# W5500.net
KiCad netlist of a schematic drawn in Altium Designer
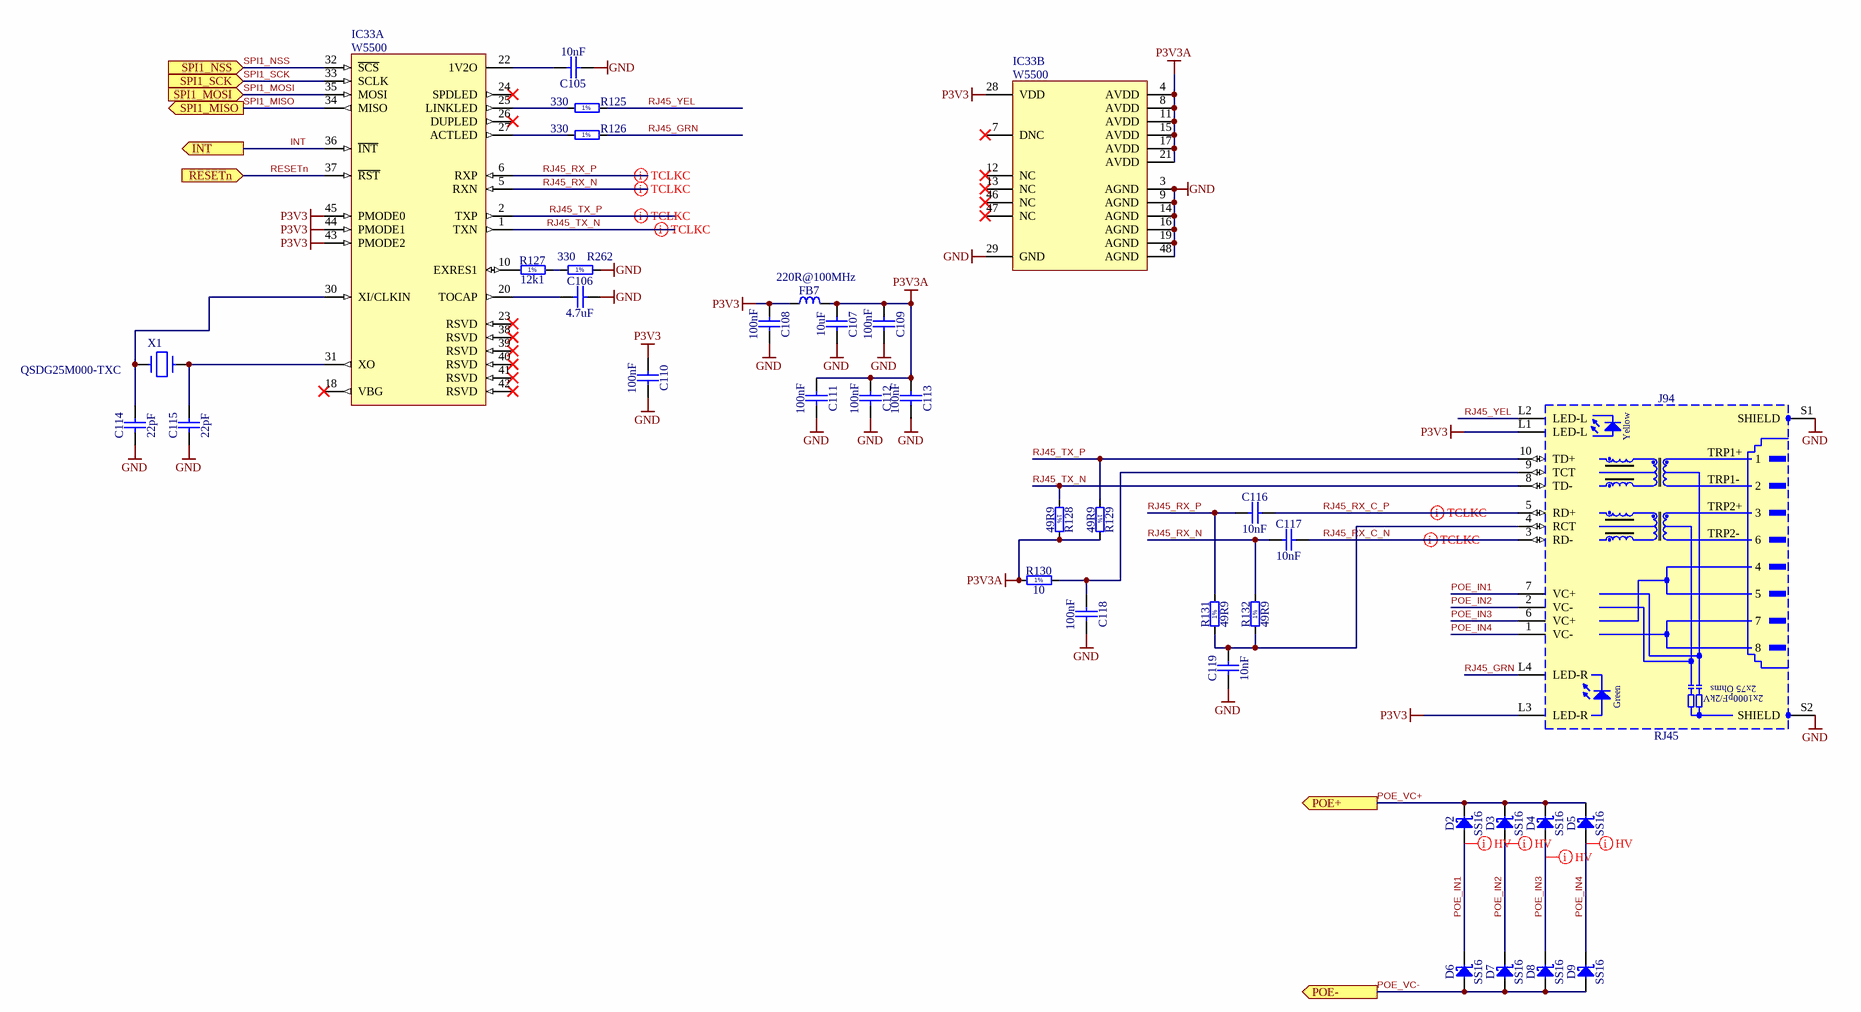
[diagram p0: W5500.SchDoc]

(export (version "E")
  (design (tool "Eeschema 10.0.6"))
  (components
    (comp (ref "C105")
      (value "10nF")
      (footprint "CAPC1608X87N")
      (description "Non-polarised capacitor")
      (fields
        (field (name "PART NUMBER") "CC0603_10NF_50V_5%_C0G")
        (field (name "VOLTAGE") "50V")
        (field (name "AUTHOR") "CERN DEM JLC")
      )
      (libsource (lib "Capacitors") (part "Capacitor - non polarized"))
    )
    (comp (ref "C106")
      (value "4.7uF")
      (footprint "CAPC1608X90N")
      (description "Non-polarised capacitor")
      (fields
        (field (name "PART NUMBER") "CC0603_4.7UF_25V_10%_X5R")
        (field (name "VOLTAGE") "25V")
        (field (name "AUTHOR") "CERN DEM JLC")
      )
      (libsource (lib "Capacitors") (part "Capacitor - non polarized"))
    )
    (comp (ref "C107")
      (value "10uF")
      (footprint "CAPC2012X135N")
      (description "Non-polarised capacitor")
      (fields
        (field (name "PART NUMBER") "CC0805_10UF_16V_10%_X5R")
        (field (name "VOLTAGE") "16V")
        (field (name "AUTHOR") "CERN DEM JLC")
      )
      (libsource (lib "Capacitors") (part "Capacitor - non polarized"))
    )
    (comp (ref "C108")
      (value "100nF")
      (footprint "CAPC1005X55N")
      (description "Non-polarised capacitor")
      (fields
        (field (name "PART NUMBER") "CC0402_100NF_16V_10%_X7R")
        (field (name "VOLTAGE") "16V")
        (field (name "AUTHOR") "CERN DEM JLC")
      )
      (libsource (lib "Capacitors") (part "Capacitor - non polarized"))
    )
    (comp (ref "C109")
      (value "100nF")
      (footprint "CAPC1005X55N")
      (description "Non-polarised capacitor")
      (fields
        (field (name "PART NUMBER") "CC0402_100NF_16V_10%_X7R")
        (field (name "VOLTAGE") "16V")
        (field (name "AUTHOR") "CERN DEM JLC")
      )
      (libsource (lib "Capacitors") (part "Capacitor - non polarized"))
    )
    (comp (ref "C110")
      (value "100nF")
      (footprint "CAPC1005X55N")
      (description "Non-polarised capacitor")
      (fields
        (field (name "PART NUMBER") "CC0402_100NF_16V_10%_X7R")
        (field (name "VOLTAGE") "16V")
        (field (name "AUTHOR") "CERN DEM JLC")
      )
      (libsource (lib "Capacitors") (part "Capacitor - non polarized"))
    )
    (comp (ref "C111")
      (value "100nF")
      (footprint "CAPC1005X55N")
      (description "Non-polarised capacitor")
      (fields
        (field (name "PART NUMBER") "CC0402_100NF_16V_10%_X7R")
        (field (name "VOLTAGE") "16V")
        (field (name "AUTHOR") "CERN DEM JLC")
      )
      (libsource (lib "Capacitors") (part "Capacitor - non polarized"))
    )
    (comp (ref "C112")
      (value "100nF")
      (footprint "CAPC1005X55N")
      (description "Non-polarised capacitor")
      (fields
        (field (name "PART NUMBER") "CC0402_100NF_16V_10%_X7R")
        (field (name "VOLTAGE") "16V")
        (field (name "AUTHOR") "CERN DEM JLC")
      )
      (libsource (lib "Capacitors") (part "Capacitor - non polarized"))
    )
    (comp (ref "C113")
      (value "100nF")
      (footprint "CAPC1005X55N")
      (description "Non-polarised capacitor")
      (fields
        (field (name "PART NUMBER") "CC0402_100NF_16V_10%_X7R")
        (field (name "VOLTAGE") "16V")
        (field (name "AUTHOR") "CERN DEM JLC")
      )
      (libsource (lib "Capacitors") (part "Capacitor - non polarized"))
    )
    (comp (ref "C114")
      (value "22pF")
      (footprint "CAPC1005X55N")
      (description "Non-polarised capacitor")
      (fields
        (field (name "PART NUMBER") "CC0402_22PF_50V_5%_NP0")
        (field (name "VOLTAGE") "50V")
        (field (name "AUTHOR") "CERN DEM JLC")
      )
      (libsource (lib "Capacitors") (part "Capacitor - non polarized"))
    )
    (comp (ref "C115")
      (value "22pF")
      (footprint "CAPC1005X55N")
      (description "Non-polarised capacitor")
      (fields
        (field (name "PART NUMBER") "CC0402_22PF_50V_5%_NP0")
        (field (name "VOLTAGE") "50V")
        (field (name "AUTHOR") "CERN DEM JLC")
      )
      (libsource (lib "Capacitors") (part "Capacitor - non polarized"))
    )
    (comp (ref "C116")
      (value "10nF")
      (footprint "CAPC1608X87N")
      (description "Non-polarised capacitor")
      (fields
        (field (name "PART NUMBER") "CC0603_10NF_50V_5%_C0G")
        (field (name "VOLTAGE") "50V")
        (field (name "AUTHOR") "CERN DEM JLC")
      )
      (libsource (lib "Capacitors") (part "Capacitor - non polarized"))
    )
    (comp (ref "C117")
      (value "10nF")
      (footprint "CAPC1608X87N")
      (description "Non-polarised capacitor")
      (fields
        (field (name "PART NUMBER") "CC0603_10NF_50V_5%_C0G")
        (field (name "VOLTAGE") "50V")
        (field (name "AUTHOR") "CERN DEM JLC")
      )
      (libsource (lib "Capacitors") (part "Capacitor - non polarized"))
    )
    (comp (ref "C118")
      (value "100nF")
      (footprint "CAPC1005X55N")
      (description "Non-polarised capacitor")
      (fields
        (field (name "PART NUMBER") "CC0402_100NF_16V_10%_X7R")
        (field (name "VOLTAGE") "16V")
        (field (name "AUTHOR") "CERN DEM JLC")
      )
      (libsource (lib "Capacitors") (part "Capacitor - non polarized"))
    )
    (comp (ref "C119")
      (value "10nF")
      (footprint "CAPC1608X87N")
      (description "Non-polarised capacitor")
      (fields
        (field (name "PART NUMBER") "CC0603_10NF_50V_5%_C0G")
        (field (name "VOLTAGE") "50V")
        (field (name "AUTHOR") "CERN DEM JLC")
      )
      (libsource (lib "Capacitors") (part "Capacitor - non polarized"))
    )
    (comp (ref "D2")
      (value "SS16")
      (footprint "DIOM5127X229N")
      (description "Schottky Diode")
      (fields
        (field (name "VOLTAGE") "60V")
        (field (name "POWER") "1A")
        (field (name "AUTHOR") "CERN DEM JLC")
      )
      (libsource (lib "ICs And Semiconductors") (part "Diode Schottky"))
    )
    (comp (ref "D3")
      (value "SS16")
      (footprint "DIOM5127X229N")
      (description "Schottky Diode")
      (fields
        (field (name "VOLTAGE") "60V")
        (field (name "POWER") "1A")
        (field (name "AUTHOR") "CERN DEM JLC")
      )
      (libsource (lib "ICs And Semiconductors") (part "Diode Schottky"))
    )
    (comp (ref "D4")
      (value "SS16")
      (footprint "DIOM5127X229N")
      (description "Schottky Diode")
      (fields
        (field (name "VOLTAGE") "60V")
        (field (name "POWER") "1A")
        (field (name "AUTHOR") "CERN DEM JLC")
      )
      (libsource (lib "ICs And Semiconductors") (part "Diode Schottky"))
    )
    (comp (ref "D5")
      (value "SS16")
      (footprint "DIOM5127X229N")
      (description "Schottky Diode")
      (fields
        (field (name "VOLTAGE") "60V")
        (field (name "POWER") "1A")
        (field (name "AUTHOR") "CERN DEM JLC")
      )
      (libsource (lib "ICs And Semiconductors") (part "Diode Schottky"))
    )
    (comp (ref "D6")
      (value "SS16")
      (footprint "DIOM5127X229N")
      (description "Schottky Diode")
      (fields
        (field (name "VOLTAGE") "60V")
        (field (name "POWER") "1A")
        (field (name "AUTHOR") "CERN DEM JLC")
      )
      (libsource (lib "ICs And Semiconductors") (part "Diode Schottky"))
    )
    (comp (ref "D7")
      (value "SS16")
      (footprint "DIOM5127X229N")
      (description "Schottky Diode")
      (fields
        (field (name "VOLTAGE") "60V")
        (field (name "POWER") "1A")
        (field (name "AUTHOR") "CERN DEM JLC")
      )
      (libsource (lib "ICs And Semiconductors") (part "Diode Schottky"))
    )
    (comp (ref "D8")
      (value "SS16")
      (footprint "DIOM5127X229N")
      (description "Schottky Diode")
      (fields
        (field (name "VOLTAGE") "60V")
        (field (name "POWER") "1A")
        (field (name "AUTHOR") "CERN DEM JLC")
      )
      (libsource (lib "ICs And Semiconductors") (part "Diode Schottky"))
    )
    (comp (ref "D9")
      (value "SS16")
      (footprint "DIOM5127X229N")
      (description "Schottky Diode")
      (fields
        (field (name "VOLTAGE") "60V")
        (field (name "POWER") "1A")
        (field (name "AUTHOR") "CERN DEM JLC")
      )
      (libsource (lib "ICs And Semiconductors") (part "Diode Schottky"))
    )
    (comp (ref "FB7")
      (value "220R@100MHz")
      (footprint "INDC2012X105N")
      (description "Inductor")
      (fields
        (field (name "PART NUMBER") "IND0805_MURATA_BLM21PG221SN1D")
        (field (name "POWER") "2A")
        (field (name "AUTHOR") "CERN DEM JLC")
      )
      (libsource (lib "Inductors & Transformers") (part "Inductor"))
    )
    (comp (ref "IC33")
      (value "W5500")
      (footprint "QFP50P900X900X160-48N")
      (description "iEthernet W5500 TCP/IP Performance and High Speed SPI Ethernet Controller")
      (fields (field (name "MANUFACTURER") "WIZNET") (field (name "AUTHOR") "CERN DEM MR"))
      (libsource (lib "ICs And Semiconductors") (part "W5500"))
    )
    (comp (ref "J94")
      (value "RJ45")
      (footprint "ABRACON_ARJM11C7-114-BA-EW2")
      (description "MagJack 10/100BaseT, PoE+, 1X1, OG/Y, -40 to 85*C, Tab Up, RoHS")
      (fields
        (field (name "PART NUMBER") "ARJM11C7-114-BA-EW2")
        (field (name "MANUFACTURER") "Abracon")
        (field (name "AUTHOR") "GK")
      )
      (libsource (lib "LIBRARY_SCH") (part "CON_ETH_POE_ARJM11C7"))
    )
    (comp (ref "R125")
      (value "330")
      (footprint "RESC1005X40N")
      (description "Resistor - 1%")
      (fields
        (field (name "PART NUMBER") "R0402_330R_1%_0.0625W_100PPM")
        (field (name "POWER") "0.0625W")
        (field (name "AUTHOR") "CERN DEM JLC")
      )
      (libsource (lib "Resistors") (part "Resistor - 1%"))
    )
    (comp (ref "R126")
      (value "330")
      (footprint "RESC1005X40N")
      (description "Resistor - 1%")
      (fields
        (field (name "PART NUMBER") "R0402_330R_1%_0.0625W_100PPM")
        (field (name "POWER") "0.0625W")
        (field (name "AUTHOR") "CERN DEM JLC")
      )
      (libsource (lib "Resistors") (part "Resistor - 1%"))
    )
    (comp (ref "R127")
      (value "12k1")
      (footprint "RESC1005X40N")
      (description "Resistor - 1%")
      (fields
        (field (name "PART NUMBER") "R0402_12K1_1%_0.0625W_100PPM")
        (field (name "POWER") "0.0625W")
        (field (name "AUTHOR") "CERN DEM JLC")
      )
      (libsource (lib "Resistors") (part "Resistor - 1%"))
    )
    (comp (ref "R128")
      (value "49R9")
      (footprint "RESC1005X40N")
      (description "Resistor - 1%")
      (fields
        (field (name "PART NUMBER") "R0402_49R9_1%_0.0625W_100PPM")
        (field (name "POWER") "0.0625W")
        (field (name "AUTHOR") "CERN DEM JLC")
      )
      (libsource (lib "Resistors") (part "Resistor - 1%"))
    )
    (comp (ref "R129")
      (value "49R9")
      (footprint "RESC1005X40N")
      (description "Resistor - 1%")
      (fields
        (field (name "PART NUMBER") "R0402_49R9_1%_0.0625W_100PPM")
        (field (name "POWER") "0.0625W")
        (field (name "AUTHOR") "CERN DEM JLC")
      )
      (libsource (lib "Resistors") (part "Resistor - 1%"))
    )
    (comp (ref "R130")
      (value "10")
      (footprint "RESC1005X40N")
      (description "Resistor - 1%")
      (fields
        (field (name "PART NUMBER") "R0402_10R_1%_0.0625W_200PPM")
        (field (name "POWER") "0.0625W")
        (field (name "AUTHOR") "CERN DEM JLC")
      )
      (libsource (lib "Resistors") (part "Resistor - 1%"))
    )
    (comp (ref "R131")
      (value "49R9")
      (footprint "RESC1005X40N")
      (description "Resistor - 1%")
      (fields
        (field (name "PART NUMBER") "R0402_49R9_1%_0.0625W_100PPM")
        (field (name "POWER") "0.0625W")
        (field (name "AUTHOR") "CERN DEM JLC")
      )
      (libsource (lib "Resistors") (part "Resistor - 1%"))
    )
    (comp (ref "R132")
      (value "49R9")
      (footprint "RESC1005X40N")
      (description "Resistor - 1%")
      (fields
        (field (name "PART NUMBER") "R0402_49R9_1%_0.0625W_100PPM")
        (field (name "POWER") "0.0625W")
        (field (name "AUTHOR") "CERN DEM JLC")
      )
      (libsource (lib "Resistors") (part "Resistor - 1%"))
    )
    (comp (ref "R262")
      (value "330")
      (footprint "RESC1005X40N")
      (description "Resistor - 1%")
      (fields
        (field (name "PART NUMBER") "R0402_330R_1%_0.0625W_100PPM")
        (field (name "POWER") "0.0625W")
        (field (name "AUTHOR") "CERN DEM JLC")
      )
      (libsource (lib "Resistors") (part "Resistor - 1%"))
    )
    (comp (ref "X1")
      (value "QSDG25M000-TXC")
      (footprint "XTAL_5.0*3.2")
      (description "miniature crystal oscillator (Maritex)")
      (libsource (lib "LIBRARY_SCH") (part "X_CRYSTAL_SMD_5.0*3.2"))
    )
  )
  (nets
    (net (code "1") (name "/INT") (class "Default")
      (node (ref "IC33") (pin "36") (pinfunction "~{INT}_36") (pintype "input"))
    )
    (net (code "2") (name "/POE_IN1") (class "Default")
      (node (ref "D2") (pin "2") (pinfunction "A_2") (pintype "passive"))
      (node (ref "D6") (pin "1") (pinfunction "C_1") (pintype "passive"))
      (node (ref "J94") (pin "7") (pinfunction "VC+_7") (pintype "passive"))
    )
    (net (code "3") (name "/POE_IN2") (class "Default")
      (node (ref "D3") (pin "2") (pinfunction "A_2") (pintype "passive"))
      (node (ref "D7") (pin "1") (pinfunction "C_1") (pintype "passive"))
      (node (ref "J94") (pin "2") (pinfunction "VC-_2") (pintype "passive"))
    )
    (net (code "4") (name "/POE_IN3") (class "Default")
      (node (ref "D4") (pin "2") (pinfunction "A_2") (pintype "passive"))
      (node (ref "D8") (pin "1") (pinfunction "C_1") (pintype "passive"))
      (node (ref "J94") (pin "6") (pinfunction "VC+_6") (pintype "passive"))
    )
    (net (code "5") (name "/POE_IN4") (class "Default")
      (node (ref "D5") (pin "2") (pinfunction "A_2") (pintype "passive"))
      (node (ref "D9") (pin "1") (pinfunction "C_1") (pintype "passive"))
      (node (ref "J94") (pin "1") (pinfunction "VC-_1") (pintype "passive"))
    )
    (net (code "6") (name "/POE_VC+") (class "Default")
      (node (ref "D2") (pin "1") (pinfunction "C_1") (pintype "passive"))
      (node (ref "D3") (pin "1") (pinfunction "C_1") (pintype "passive"))
      (node (ref "D4") (pin "1") (pinfunction "C_1") (pintype "passive"))
      (node (ref "D5") (pin "1") (pinfunction "C_1") (pintype "passive"))
    )
    (net (code "7") (name "/POE_VC-") (class "Default")
      (node (ref "D6") (pin "2") (pinfunction "A_2") (pintype "passive"))
      (node (ref "D7") (pin "2") (pinfunction "A_2") (pintype "passive"))
      (node (ref "D8") (pin "2") (pinfunction "A_2") (pintype "passive"))
      (node (ref "D9") (pin "2") (pinfunction "A_2") (pintype "passive"))
    )
    (net (code "8") (name "/RESETn") (class "Default")
      (node (ref "IC33") (pin "37") (pinfunction "~{RST}_37") (pintype "input"))
    )
    (net (code "9") (name "/RJ45_GRN") (class "Default")
      (node (ref "J94") (pin "L4") (pinfunction "LED-R_L4") (pintype "passive"))
      (node (ref "R126") (pin "2") (pinfunction "2_2") (pintype "passive"))
    )
    (net (code "10") (name "/RJ45_RX_C_N") (class "Default")
      (node (ref "C117") (pin "2") (pinfunction "2_2") (pintype "passive"))
      (node (ref "J94") (pin "3") (pinfunction "RD-_3") (pintype "bidirectional"))
    )
    (net (code "11") (name "/RJ45_RX_C_P") (class "Default")
      (node (ref "C116") (pin "2") (pinfunction "2_2") (pintype "passive"))
      (node (ref "J94") (pin "5") (pinfunction "RD+_5") (pintype "bidirectional"))
    )
    (net (code "12") (name "/RJ45_RX_N") (class "Default")
      (node (ref "C117") (pin "1") (pinfunction "1_1") (pintype "passive"))
      (node (ref "IC33") (pin "5") (pinfunction "RXN_5") (pintype "input"))
      (node (ref "R132") (pin "2") (pinfunction "2_2") (pintype "passive"))
    )
    (net (code "13") (name "/RJ45_RX_P") (class "Default")
      (node (ref "C116") (pin "1") (pinfunction "1_1") (pintype "passive"))
      (node (ref "IC33") (pin "6") (pinfunction "RXP_6") (pintype "input"))
      (node (ref "R131") (pin "2") (pinfunction "2_2") (pintype "passive"))
    )
    (net (code "14") (name "/RJ45_TX_N") (class "Default")
      (node (ref "IC33") (pin "1") (pinfunction "TXN_1") (pintype "output"))
      (node (ref "J94") (pin "8") (pinfunction "TD-_8") (pintype "bidirectional"))
      (node (ref "R128") (pin "1") (pinfunction "1_1") (pintype "passive"))
    )
    (net (code "15") (name "/RJ45_TX_P") (class "Default")
      (node (ref "IC33") (pin "2") (pinfunction "TXP_2") (pintype "output"))
      (node (ref "J94") (pin "10") (pinfunction "TD+_10") (pintype "bidirectional"))
      (node (ref "R129") (pin "1") (pinfunction "1_1") (pintype "passive"))
    )
    (net (code "16") (name "/RJ45_YEL") (class "Default")
      (node (ref "J94") (pin "L2") (pinfunction "LED-L_L2") (pintype "passive"))
      (node (ref "R125") (pin "2") (pinfunction "2_2") (pintype "passive"))
    )
    (net (code "17") (name "/SPI1_MISO") (class "Default")
      (node (ref "IC33") (pin "34") (pinfunction "MISO_34") (pintype "output"))
    )
    (net (code "18") (name "/SPI1_MOSI") (class "Default")
      (node (ref "IC33") (pin "35") (pinfunction "MOSI_35") (pintype "input"))
    )
    (net (code "19") (name "/SPI1_NSS") (class "Default")
      (node (ref "IC33") (pin "32") (pinfunction "~{SCS}_32") (pintype "input"))
    )
    (net (code "20") (name "/SPI1_SCK") (class "Default")
      (node (ref "IC33") (pin "33") (pinfunction "SCLK_33") (pintype "input"))
    )
    (net (code "21") (name "GND") (class "Default")
      (node (ref "C105") (pin "1") (pinfunction "1_1") (pintype "passive"))
      (node (ref "C106") (pin "2") (pinfunction "2_2") (pintype "passive"))
      (node (ref "C107") (pin "2") (pinfunction "2_2") (pintype "passive"))
      (node (ref "C108") (pin "2") (pinfunction "2_2") (pintype "passive"))
      (node (ref "C109") (pin "2") (pinfunction "2_2") (pintype "passive"))
      (node (ref "C110") (pin "2") (pinfunction "2_2") (pintype "passive"))
      (node (ref "C111") (pin "2") (pinfunction "2_2") (pintype "passive"))
      (node (ref "C112") (pin "2") (pinfunction "2_2") (pintype "passive"))
      (node (ref "C113") (pin "2") (pinfunction "2_2") (pintype "passive"))
      (node (ref "C114") (pin "1") (pinfunction "1_1") (pintype "passive"))
      (node (ref "C115") (pin "1") (pinfunction "1_1") (pintype "passive"))
      (node (ref "C118") (pin "2") (pinfunction "2_2") (pintype "passive"))
      (node (ref "C119") (pin "1") (pinfunction "1_1") (pintype "passive"))
      (node (ref "IC33") (pin "14") (pinfunction "AGND_14") (pintype "power_in"))
      (node (ref "IC33") (pin "16") (pinfunction "AGND_16") (pintype "power_in"))
      (node (ref "IC33") (pin "19") (pinfunction "AGND_19") (pintype "power_in"))
      (node (ref "IC33") (pin "29") (pinfunction "GND_29") (pintype "power_in"))
      (node (ref "IC33") (pin "3") (pinfunction "AGND_3") (pintype "power_in"))
      (node (ref "IC33") (pin "48") (pinfunction "AGND_48") (pintype "power_in"))
      (node (ref "IC33") (pin "9") (pinfunction "AGND_9") (pintype "power_in"))
      (node (ref "J94") (pin "S1") (pinfunction "SHIELD_S1") (pintype "power_in"))
      (node (ref "J94") (pin "S2") (pinfunction "SHIELD_S2") (pintype "power_in"))
      (node (ref "R262") (pin "2") (pinfunction "2_2") (pintype "passive"))
    )
    (net (code "22") (name "Net-(IC33A-1V2O)") (class "Default")
      (node (ref "C105") (pin "2") (pinfunction "2_2") (pintype "passive"))
      (node (ref "IC33") (pin "22") (pinfunction "1V2O_22") (pintype "power_in"))
    )
    (net (code "23") (name "Net-(IC33A-ACTLED)") (class "Default")
      (node (ref "IC33") (pin "27") (pinfunction "ACTLED_27") (pintype "output"))
      (node (ref "R126") (pin "1") (pinfunction "1_1") (pintype "passive"))
    )
    (net (code "24") (name "Net-(IC33A-EXRES1)") (class "Default")
      (node (ref "IC33") (pin "10") (pinfunction "EXRES1_10") (pintype "bidirectional"))
      (node (ref "R127") (pin "1") (pinfunction "1_1") (pintype "passive"))
    )
    (net (code "25") (name "Net-(IC33A-LINKLED)") (class "Default")
      (node (ref "IC33") (pin "25") (pinfunction "LINKLED_25") (pintype "output"))
      (node (ref "R125") (pin "1") (pinfunction "1_1") (pintype "passive"))
    )
    (net (code "26") (name "Net-(IC33A-TOCAP)") (class "Default")
      (node (ref "C106") (pin "1") (pinfunction "1_1") (pintype "passive"))
      (node (ref "IC33") (pin "20") (pinfunction "TOCAP_20") (pintype "output"))
    )
    (net (code "27") (name "Net-(IC33A-XI{slash}CLKIN)") (class "Default")
      (node (ref "C114") (pin "2") (pinfunction "2_2") (pintype "passive"))
      (node (ref "IC33") (pin "30") (pinfunction "XI/CLKIN_30") (pintype "input"))
      (node (ref "X1") (pin "1") (pinfunction "1_1") (pintype "passive"))
    )
    (net (code "28") (name "Net-(IC33A-XO)") (class "Default")
      (node (ref "C115") (pin "2") (pinfunction "2_2") (pintype "passive"))
      (node (ref "IC33") (pin "31") (pinfunction "XO_31") (pintype "output"))
      (node (ref "X1") (pin "2") (pinfunction "2_2") (pintype "passive"))
    )
    (net (code "29") (name "Net-(J94-RCT)") (class "Default")
      (node (ref "C119") (pin "2") (pinfunction "2_2") (pintype "passive"))
      (node (ref "J94") (pin "4") (pinfunction "RCT_4") (pintype "bidirectional"))
      (node (ref "R131") (pin "1") (pinfunction "1_1") (pintype "passive"))
      (node (ref "R132") (pin "1") (pinfunction "1_1") (pintype "passive"))
    )
    (net (code "30") (name "Net-(J94-TCT)") (class "Default")
      (node (ref "C118") (pin "1") (pinfunction "1_1") (pintype "passive"))
      (node (ref "J94") (pin "9") (pinfunction "TCT_9") (pintype "bidirectional"))
      (node (ref "R130") (pin "2") (pinfunction "2_2") (pintype "passive"))
    )
    (net (code "31") (name "Net-(R127-Pad2)") (class "Default")
      (node (ref "R127") (pin "2") (pinfunction "2_2") (pintype "passive"))
      (node (ref "R262") (pin "1") (pinfunction "1_1") (pintype "passive"))
    )
    (net (code "32") (name "P3V3") (class "Default")
      (node (ref "C108") (pin "1") (pinfunction "1_1") (pintype "passive"))
      (node (ref "C110") (pin "1") (pinfunction "1_1") (pintype "passive"))
      (node (ref "FB7") (pin "1") (pinfunction "1_1") (pintype "passive"))
      (node (ref "IC33") (pin "28") (pinfunction "VDD_28") (pintype "power_in"))
      (node (ref "IC33") (pin "43") (pinfunction "PMODE2_43") (pintype "input"))
      (node (ref "IC33") (pin "44") (pinfunction "PMODE1_44") (pintype "input"))
      (node (ref "IC33") (pin "45") (pinfunction "PMODE0_45") (pintype "input"))
      (node (ref "J94") (pin "L1") (pinfunction "LED-L_L1") (pintype "passive"))
      (node (ref "J94") (pin "L3") (pinfunction "LED-R_L3") (pintype "passive"))
    )
    (net (code "33") (name "P3V3A") (class "Default")
      (node (ref "C107") (pin "1") (pinfunction "1_1") (pintype "passive"))
      (node (ref "C109") (pin "1") (pinfunction "1_1") (pintype "passive"))
      (node (ref "C111") (pin "1") (pinfunction "1_1") (pintype "passive"))
      (node (ref "C112") (pin "1") (pinfunction "1_1") (pintype "passive"))
      (node (ref "C113") (pin "1") (pinfunction "1_1") (pintype "passive"))
      (node (ref "FB7") (pin "2") (pinfunction "2_2") (pintype "passive"))
      (node (ref "IC33") (pin "11") (pinfunction "AVDD_11") (pintype "power_in"))
      (node (ref "IC33") (pin "15") (pinfunction "AVDD_15") (pintype "power_in"))
      (node (ref "IC33") (pin "17") (pinfunction "AVDD_17") (pintype "power_in"))
      (node (ref "IC33") (pin "21") (pinfunction "AVDD_21") (pintype "power_in"))
      (node (ref "IC33") (pin "4") (pinfunction "AVDD_4") (pintype "power_in"))
      (node (ref "IC33") (pin "8") (pinfunction "AVDD_8") (pintype "power_in"))
      (node (ref "R128") (pin "2") (pinfunction "2_2") (pintype "passive"))
      (node (ref "R129") (pin "2") (pinfunction "2_2") (pintype "passive"))
      (node (ref "R130") (pin "1") (pinfunction "1_1") (pintype "passive"))
    )
    (net (code "34") (name "unconnected-(IC33A-DUPLED-Pad26)") (class "Default")
      (node (ref "IC33") (pin "26") (pinfunction "DUPLED_26") (pintype "output+no_connect"))
    )
    (net (code "35") (name "unconnected-(IC33A-RSVD-Pad23)") (class "Default")
      (node (ref "IC33") (pin "23") (pinfunction "RSVD_23") (pintype "input+no_connect"))
    )
    (net (code "36") (name "unconnected-(IC33A-RSVD-Pad38)") (class "Default")
      (node (ref "IC33") (pin "38") (pinfunction "RSVD_38") (pintype "input+no_connect"))
    )
    (net (code "37") (name "unconnected-(IC33A-RSVD-Pad39)") (class "Default")
      (node (ref "IC33") (pin "39") (pinfunction "RSVD_39") (pintype "input+no_connect"))
    )
    (net (code "38") (name "unconnected-(IC33A-RSVD-Pad40)") (class "Default")
      (node (ref "IC33") (pin "40") (pinfunction "RSVD_40") (pintype "input+no_connect"))
    )
    (net (code "39") (name "unconnected-(IC33A-RSVD-Pad41)") (class "Default")
      (node (ref "IC33") (pin "41") (pinfunction "RSVD_41") (pintype "input+no_connect"))
    )
    (net (code "40") (name "unconnected-(IC33A-RSVD-Pad42)") (class "Default")
      (node (ref "IC33") (pin "42") (pinfunction "RSVD_42") (pintype "input+no_connect"))
    )
    (net (code "41") (name "unconnected-(IC33A-SPDLED-Pad24)") (class "Default")
      (node (ref "IC33") (pin "24") (pinfunction "SPDLED_24") (pintype "output+no_connect"))
    )
    (net (code "42") (name "unconnected-(IC33A-VBG-Pad18)") (class "Default")
      (node (ref "IC33") (pin "18") (pinfunction "VBG_18") (pintype "output+no_connect"))
    )
    (net (code "43") (name "unconnected-(IC33B-DNC-Pad7)") (class "Default")
      (node (ref "IC33") (pin "7") (pinfunction "DNC_7") (pintype "passive+no_connect"))
    )
    (net (code "44") (name "unconnected-(IC33B-NC-Pad12)") (class "Default")
      (node (ref "IC33") (pin "12") (pinfunction "NC_12") (pintype "passive+no_connect"))
    )
    (net (code "45") (name "unconnected-(IC33B-NC-Pad13)") (class "Default")
      (node (ref "IC33") (pin "13") (pinfunction "NC_13") (pintype "passive+no_connect"))
    )
    (net (code "46") (name "unconnected-(IC33B-NC-Pad46)") (class "Default")
      (node (ref "IC33") (pin "46") (pinfunction "NC_46") (pintype "passive+no_connect"))
    )
    (net (code "47") (name "unconnected-(IC33B-NC-Pad47)") (class "Default")
      (node (ref "IC33") (pin "47") (pinfunction "NC_47") (pintype "passive+no_connect"))
    )
  )
)
